# AD8232.net
KiCad netlist of a schematic drawn in Altium Designer
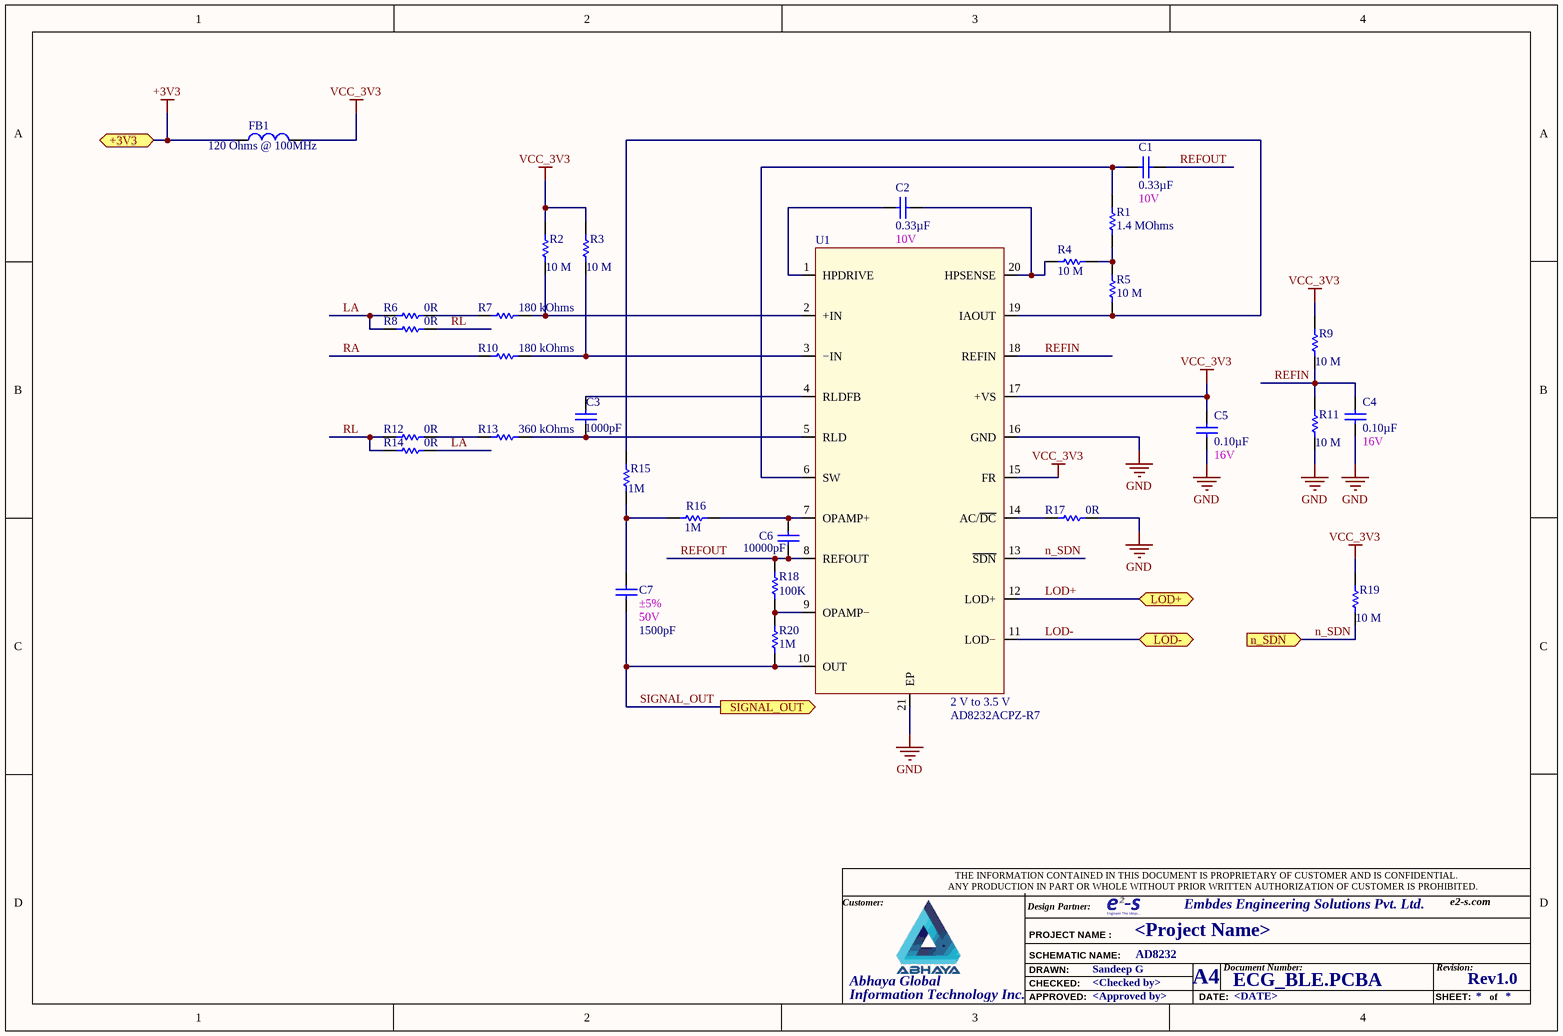
[diagram p0: AD8232.SchDoc]

(export (version "E")
  (design (tool "Eeschema 10.0.6"))
  (components
    (comp (ref "C1")
      (value "0.33µF")
      (footprint "SMDC0402")
      (description "CAP CER 0.33UF 10V X5R 0402")
      (fields
        (field (name "MANUFACTURER") "Samsung Electro-Mechanics")
        (field (name "MANUFACTURER PART NUMBER") "CL05A334KP5NNNC")
        (field (name "1ST AUXILIARY FIELD") "10V")
      )
      (libsource (lib "ECG_BLE") (part "ECA0U33L10V0-SB"))
    )
    (comp (ref "C2")
      (value "0.33µF")
      (footprint "SMDC0402")
      (description "CAP CER 0.33UF 10V X5R 0402")
      (fields
        (field (name "MANUFACTURER") "Samsung Electro-Mechanics")
        (field (name "MANUFACTURER PART NUMBER") "CL05A334KP5NNNC")
        (field (name "1ST AUXILIARY FIELD") "10V")
      )
      (libsource (lib "ECG_BLE") (part "ECA0U33L10V0-SB"))
    )
    (comp (ref "C3")
      (value "1000pF")
      (footprint "SMDC0402")
      (description "CAP CER 1000PF 50V X7R 0402")
      (fields
        (field (name "MANUFACTURER") "KEMET")
        (field (name "MANUFACTURER PART NUMBER") "C0402C102J5RACTU")
      )
      (libsource (lib "ECG_BLE") (part "ECA1N00K50V0-SB"))
    )
    (comp (ref "C4")
      (value "0.10µF")
      (footprint "SMDC0402")
      (description "CAP CER 0.1UF 16V X7R 0402")
      (fields
        (field (name "MANUFACTURER") "Samsung Electro-Mechanics America, Inc.")
        (field (name "MANUFACTURER PART NUMBER") "CL05B104KO5NNNC")
        (field (name "1ST AUXILIARY FIELD") "16V")
      )
      (libsource (lib "Master_ Library") (part "ECA0U10K16V0-1-SB"))
    )
    (comp (ref "C5")
      (value "0.10µF")
      (footprint "SMDC0402")
      (description "CAP CER 0.1UF 16V X7R 0402")
      (fields
        (field (name "MANUFACTURER") "Samsung Electro-Mechanics America, Inc.")
        (field (name "MANUFACTURER PART NUMBER") "CL05B104KO5NNNC")
        (field (name "1ST AUXILIARY FIELD") "16V")
      )
      (libsource (lib "Master_ Library") (part "ECA0U10K16V0-1-SB"))
    )
    (comp (ref "C6")
      (value "10000pF")
      (footprint "SMDCC0402")
      (description "CAP CER 10000PF 50V X7R 0402")
      (fields
        (field (name "MANUFACTURER PART NUMBER") "C0402C103J5RACTU")
        (field (name "MANUFACTURER") "Samsung Electro-Mechanics America, Inc.")
      )
      (libsource (lib "Master_ Library") (part "ECA10N0K50V0-SB"))
    )
    (comp (ref "C7")
      (value "1500pF")
      (footprint "SMDC0402")
      (description "CAP CER 1500PF 50V X7R 0402")
      (fields
        (field (name "MANUFACTURER") "Yageo")
        (field (name "VENDOR PART NUMBER") "311-3763-1-ND")
        (field (name "2ND AUXILIARY FIELD") "±5%")
        (field (name "1ST AUXILIARY FIELD") "50V")
      )
      (libsource (lib "ECG_BLE") (part "ECA1N50K50V0-SB"))
    )
    (comp (ref "FB1")
      (value "120 Ohms @ 100MHz")
      (footprint "Master_Library:SMDL0402")
      (description "FERRITE BEAD 120 OHM 0402 1LN")
      (fields
        (field (name "MANUFACTURER PART NUMBER") "BLM15PX121SN1D")
        (field (name "MANUFACTURER") "Murata Electronics")
      )
      (libsource (lib "ECG_BLE") (part "EMS-BLM15PX121SN1D"))
    )
    (comp (ref "R1")
      (value "1.4 MOhms")
      (footprint "Master_Library:SMDR0402")
      (description "RES 1.4M OHM 1% 1/16W 0402")
      (fields
        (field (name "MANUFACTURER") "Stackpole Electronics Inc")
        (field (name "VENDOR PART NUMBER") "RMCF0402FT1M40CT-ND")
      )
      (libsource (lib "ECG_BLE") (part "ERE1M40G116-SB"))
    )
    (comp (ref "R2")
      (value "10 M")
      (footprint "SMDR0402")
      (description "RES SMD 10M OHM 5% 1/10W 0402")
      (fields
        (field (name "MANUFACTURER PART NUMBER") "ERJ-2GEJ106X")
        (field (name "MANUFACTURER") "Panasonic Electronic Components")
      )
      (libsource (lib "Master_ Library") (part "ERE10M0K110-SB"))
    )
    (comp (ref "R3")
      (value "10 M")
      (footprint "SMDR0402")
      (description "RES SMD 10M OHM 5% 1/10W 0402")
      (fields
        (field (name "MANUFACTURER PART NUMBER") "ERJ-2GEJ106X")
        (field (name "MANUFACTURER") "Panasonic Electronic Components")
      )
      (libsource (lib "Master_ Library") (part "ERE10M0K110-SB"))
    )
    (comp (ref "R4")
      (value "10 M")
      (footprint "SMDR0402")
      (description "RES SMD 10M OHM 5% 1/10W 0402")
      (fields
        (field (name "MANUFACTURER PART NUMBER") "ERJ-2GEJ106X")
        (field (name "MANUFACTURER") "Panasonic Electronic Components")
      )
      (libsource (lib "Master_ Library") (part "ERE10M0K110-SB"))
    )
    (comp (ref "R5")
      (value "10 M")
      (footprint "SMDR0402")
      (description "RES SMD 10M OHM 5% 1/10W 0402")
      (fields
        (field (name "MANUFACTURER PART NUMBER") "ERJ-2GEJ106X")
        (field (name "MANUFACTURER") "Panasonic Electronic Components")
      )
      (libsource (lib "Master_ Library") (part "ERE10M0K110-SB"))
    )
    (comp (ref "R6")
      (value "0R")
      (footprint "Master_Library:SMDR0402")
      (description "RES SMD 0.0OHM JUMPER 1/10W 0402")
      (fields
        (field (name "MANUFACTURER") "Panasonic Electronic Components")
        (field (name "VENDOR PART NUMBER") "P0.0JCT-ND")
      )
      (libsource (lib "Integrated_Master_Library") (part "ERE0R00110-SB"))
    )
    (comp (ref "R7")
      (value "180 kOhms")
      (footprint "Master_Library:SMDR0402")
      (description "RES SMD 180K OHM 1% 1/16W 0402")
      (fields (field (name "MANUFACTURER") "Yageo") (field (name "VENDOR PART NUMBER") "311-180KLRCT-ND"))
      (libsource (lib "ECG_BLE") (part "ERE180KG116-SB"))
    )
    (comp (ref "R8")
      (value "0R")
      (footprint "Master_Library:SMDR0402")
      (description "RES SMD 0.0OHM JUMPER 1/10W 0402")
      (fields
        (field (name "MANUFACTURER") "Panasonic Electronic Components")
        (field (name "VENDOR PART NUMBER") "P0.0JCT-ND")
      )
      (libsource (lib "Integrated_Master_Library") (part "ERE0R00110-SB"))
    )
    (comp (ref "R9")
      (value "10 M")
      (footprint "SMDR0402")
      (description "RES SMD 10M OHM 5% 1/10W 0402")
      (fields
        (field (name "MANUFACTURER PART NUMBER") "ERJ-2GEJ106X")
        (field (name "MANUFACTURER") "Panasonic Electronic Components")
      )
      (libsource (lib "Master_ Library") (part "ERE10M0K110-SB"))
    )
    (comp (ref "R10")
      (value "180 kOhms")
      (footprint "Master_Library:SMDR0402")
      (description "RES SMD 180K OHM 1% 1/16W 0402")
      (fields (field (name "MANUFACTURER") "Yageo") (field (name "VENDOR PART NUMBER") "311-180KLRCT-ND"))
      (libsource (lib "ECG_BLE") (part "ERE180KG116-SB"))
    )
    (comp (ref "R11")
      (value "10 M")
      (footprint "SMDR0402")
      (description "RES SMD 10M OHM 5% 1/10W 0402")
      (fields
        (field (name "MANUFACTURER PART NUMBER") "ERJ-2GEJ106X")
        (field (name "MANUFACTURER") "Panasonic Electronic Components")
      )
      (libsource (lib "Master_ Library") (part "ERE10M0K110-SB"))
    )
    (comp (ref "R12")
      (value "0R")
      (footprint "Master_Library:SMDR0402")
      (description "RES SMD 0.0OHM JUMPER 1/10W 0402")
      (fields
        (field (name "MANUFACTURER") "Panasonic Electronic Components")
        (field (name "VENDOR PART NUMBER") "P0.0JCT-ND")
      )
      (libsource (lib "Integrated_Master_Library") (part "ERE0R00110-SB"))
    )
    (comp (ref "R13")
      (value "360 kOhms")
      (footprint "Master_Library:SMDR0402")
      (description "RES SMD 360K OHM 1% 1/10W 0402")
      (fields
        (field (name "MANUFACTURER") "Panasonic Electronic Components")
        (field (name "VENDOR PART NUMBER") "P360KLCT-ND")
      )
      (libsource (lib "ECG_BLE") (part "ERE360KG110-SB"))
    )
    (comp (ref "R14")
      (value "0R")
      (footprint "Master_Library:SMDR0402")
      (description "RES SMD 0.0OHM JUMPER 1/10W 0402")
      (fields
        (field (name "MANUFACTURER") "Panasonic Electronic Components")
        (field (name "VENDOR PART NUMBER") "P0.0JCT-ND")
      )
      (libsource (lib "Integrated_Master_Library") (part "ERE0R00110-SB"))
    )
    (comp (ref "R15")
      (value "1M")
      (footprint "SMDR0402")
      (description "RES SMD 1M OHM 1% 1/10W 0402")
      (fields
        (field (name "MANUFACTURER PART NUMBER") "ERJ-2RKF1004X")
        (field (name "MANUFACTURER") "Panasonic Electronic Components")
      )
      (libsource (lib "Master_ Library") (part "ERE1M00G110-SB"))
    )
    (comp (ref "R16")
      (value "1M")
      (footprint "SMDR0402")
      (description "RES SMD 1M OHM 1% 1/10W 0402")
      (fields
        (field (name "MANUFACTURER PART NUMBER") "ERJ-2RKF1004X")
        (field (name "MANUFACTURER") "Panasonic Electronic Components")
      )
      (libsource (lib "Master_ Library") (part "ERE1M00G110-SB"))
    )
    (comp (ref "R17")
      (value "0R")
      (footprint "Master_Library:SMDR0402")
      (description "RES SMD 0.0OHM JUMPER 1/10W 0402")
      (fields
        (field (name "MANUFACTURER") "Panasonic Electronic Components")
        (field (name "VENDOR PART NUMBER") "P0.0JCT-ND")
      )
      (libsource (lib "Integrated_Master_Library") (part "ERE0R00110-SB"))
    )
    (comp (ref "R18")
      (value "100K")
      (footprint "SMDRC0402")
      (description "RES SMD 100K OHM 1% 1/10W 0402")
      (fields
        (field (name "MANUFACTURER PART NUMBER") "ERJ-2RKF1003X")
        (field (name "MANUFACTURER") "Panasonic Electronic Components")
      )
      (libsource (lib "Master_ Library") (part "ERE100KG110-SB"))
    )
    (comp (ref "R19")
      (value "10 M")
      (footprint "SMDR0402")
      (description "RES SMD 10M OHM 5% 1/10W 0402")
      (fields
        (field (name "MANUFACTURER PART NUMBER") "ERJ-2GEJ106X")
        (field (name "MANUFACTURER") "Panasonic Electronic Components")
      )
      (libsource (lib "Master_ Library") (part "ERE10M0K110-SB"))
    )
    (comp (ref "R20")
      (value "1M")
      (footprint "SMDR0402")
      (description "RES SMD 1M OHM 1% 1/10W 0402")
      (fields
        (field (name "MANUFACTURER PART NUMBER") "ERJ-2RKF1004X")
        (field (name "MANUFACTURER") "Panasonic Electronic Components")
      )
      (libsource (lib "Master_ Library") (part "ERE1M00G110-SB"))
    )
    (comp (ref "U1")
      (value "AD8232ACPZ-R7")
      (description "Analog Front End - AFE ECG and HRM IC Single Lead")
      (fields
        (field (name "INTERNAL PART NUMBER") "EICADLFCSP-20-****")
        (field (name "MANUFACTURER") "Analog Devices")
        (field (name "1ST AUXILIARY FIELD") "2 V to 3.5 V")
      )
      (libsource (lib "ECG_BLE") (part "EICADLFCSP-20-****"))
    )
  )
  (nets
    (net (code "1") (name "+3V3") (class "Default")
      (node (ref "FB1") (pin "1") (pinfunction "1_1") (pintype "passive"))
    )
    (net (code "2") (name "/LA") (class "Default")
      (node (ref "R14") (pin "2") (pinfunction "2_2") (pintype "passive"))
      (node (ref "R6") (pin "1") (pinfunction "1_1") (pintype "passive"))
      (node (ref "R8") (pin "1") (pinfunction "1_1") (pintype "passive"))
    )
    (net (code "3") (name "/LOD+") (class "Default")
      (node (ref "U1") (pin "12") (pinfunction "LOD+_12") (pintype "passive"))
    )
    (net (code "4") (name "/LOD-") (class "Default")
      (node (ref "U1") (pin "11") (pinfunction "LOD−_11") (pintype "passive"))
    )
    (net (code "5") (name "/RA") (class "Default")
      (node (ref "R10") (pin "1") (pinfunction "1_1") (pintype "passive"))
    )
    (net (code "6") (name "/REFIN") (class "Default")
      (node (ref "C4") (pin "2") (pinfunction "2_2") (pintype "passive"))
      (node (ref "R11") (pin "2") (pinfunction "2_2") (pintype "passive"))
      (node (ref "R9") (pin "1") (pinfunction "1_1") (pintype "passive"))
      (node (ref "U1") (pin "18") (pinfunction "REFIN_18") (pintype "passive"))
    )
    (net (code "7") (name "/REFOUT") (class "Default")
      (node (ref "C1") (pin "2") (pinfunction "2_2") (pintype "passive"))
      (node (ref "C6") (pin "1") (pinfunction "1_1") (pintype "passive"))
      (node (ref "R18") (pin "1") (pinfunction "1_1") (pintype "passive"))
      (node (ref "U1") (pin "8") (pinfunction "REFOUT_8") (pintype "passive"))
    )
    (net (code "8") (name "/RL") (class "Default")
      (node (ref "R12") (pin "1") (pinfunction "1_1") (pintype "passive"))
      (node (ref "R14") (pin "1") (pinfunction "1_1") (pintype "passive"))
      (node (ref "R8") (pin "2") (pinfunction "2_2") (pintype "passive"))
    )
    (net (code "9") (name "/SIGNAL_OUT") (class "Default")
      (node (ref "C7") (pin "1") (pinfunction "1_1") (pintype "passive"))
      (node (ref "R20") (pin "2") (pinfunction "2_2") (pintype "passive"))
      (node (ref "U1") (pin "10") (pinfunction "OUT_10") (pintype "passive"))
    )
    (net (code "10") (name "/n_SDN") (class "Default")
      (node (ref "R19") (pin "1") (pinfunction "1_1") (pintype "passive"))
      (node (ref "U1") (pin "13") (pinfunction "~{SDN}_13") (pintype "passive"))
    )
    (net (code "11") (name "GND") (class "Default")
      (node (ref "C4") (pin "1") (pinfunction "1_1") (pintype "passive"))
      (node (ref "C5") (pin "1") (pinfunction "1_1") (pintype "passive"))
      (node (ref "R11") (pin "1") (pinfunction "1_1") (pintype "passive"))
      (node (ref "R17") (pin "2") (pinfunction "2_2") (pintype "passive"))
      (node (ref "U1") (pin "16") (pinfunction "GND_16") (pintype "passive"))
      (node (ref "U1") (pin "21") (pinfunction "EP_21") (pintype "passive"))
    )
    (net (code "12") (name "Net-(C7-Pad2)") (class "Default")
      (node (ref "C7") (pin "2") (pinfunction "2_2") (pintype "passive"))
      (node (ref "R15") (pin "1") (pinfunction "1_1") (pintype "passive"))
      (node (ref "R16") (pin "2") (pinfunction "2_2") (pintype "passive"))
    )
    (net (code "13") (name "Net-(R1-Pad1)") (class "Default")
      (node (ref "R1") (pin "1") (pinfunction "1_1") (pintype "passive"))
      (node (ref "R4") (pin "1") (pinfunction "1_1") (pintype "passive"))
      (node (ref "R5") (pin "1") (pinfunction "1_1") (pintype "passive"))
    )
    (net (code "14") (name "Net-(R6-Pad2)") (class "Default")
      (node (ref "R6") (pin "2") (pinfunction "2_2") (pintype "passive"))
      (node (ref "R7") (pin "1") (pinfunction "1_1") (pintype "passive"))
    )
    (net (code "15") (name "Net-(R12-Pad2)") (class "Default")
      (node (ref "R12") (pin "2") (pinfunction "2_2") (pintype "passive"))
      (node (ref "R13") (pin "1") (pinfunction "1_1") (pintype "passive"))
    )
    (net (code "16") (name "Net-(U1-+IN)") (class "Default")
      (node (ref "R2") (pin "1") (pinfunction "1_1") (pintype "passive"))
      (node (ref "R7") (pin "2") (pinfunction "2_2") (pintype "passive"))
      (node (ref "U1") (pin "2") (pinfunction "+IN_2") (pintype "passive"))
    )
    (net (code "17") (name "Net-(U1-AC{slash}~{DC})") (class "Default")
      (node (ref "R17") (pin "1") (pinfunction "1_1") (pintype "passive"))
      (node (ref "U1") (pin "14") (pinfunction "AC/~{DC}_14") (pintype "passive"))
    )
    (net (code "18") (name "Net-(U1-HPDRIVE)") (class "Default")
      (node (ref "C2") (pin "1") (pinfunction "1_1") (pintype "passive"))
      (node (ref "U1") (pin "1") (pinfunction "HPDRIVE_1") (pintype "passive"))
    )
    (net (code "19") (name "Net-(U1-HPSENSE)") (class "Default")
      (node (ref "C2") (pin "2") (pinfunction "2_2") (pintype "passive"))
      (node (ref "R4") (pin "2") (pinfunction "2_2") (pintype "passive"))
      (node (ref "U1") (pin "20") (pinfunction "HPSENSE_20") (pintype "passive"))
    )
    (net (code "20") (name "Net-(U1-IAOUT)") (class "Default")
      (node (ref "R15") (pin "2") (pinfunction "2_2") (pintype "passive"))
      (node (ref "R5") (pin "2") (pinfunction "2_2") (pintype "passive"))
      (node (ref "U1") (pin "19") (pinfunction "IAOUT_19") (pintype "passive"))
    )
    (net (code "21") (name "Net-(U1-OPAMP+)") (class "Default")
      (node (ref "C6") (pin "2") (pinfunction "2_2") (pintype "passive"))
      (node (ref "R16") (pin "1") (pinfunction "1_1") (pintype "passive"))
      (node (ref "U1") (pin "7") (pinfunction "OPAMP+_7") (pintype "passive"))
    )
    (net (code "22") (name "Net-(U1-OPAMP−)") (class "Default")
      (node (ref "R18") (pin "2") (pinfunction "2_2") (pintype "passive"))
      (node (ref "R20") (pin "1") (pinfunction "1_1") (pintype "passive"))
      (node (ref "U1") (pin "9") (pinfunction "OPAMP−_9") (pintype "passive"))
    )
    (net (code "23") (name "Net-(U1-RLD)") (class "Default")
      (node (ref "C3") (pin "1") (pinfunction "1_1") (pintype "passive"))
      (node (ref "R13") (pin "2") (pinfunction "2_2") (pintype "passive"))
      (node (ref "U1") (pin "5") (pinfunction "RLD_5") (pintype "passive"))
    )
    (net (code "24") (name "Net-(U1-RLDFB)") (class "Default")
      (node (ref "C3") (pin "2") (pinfunction "2_2") (pintype "passive"))
      (node (ref "U1") (pin "4") (pinfunction "RLDFB_4") (pintype "passive"))
    )
    (net (code "25") (name "Net-(U1-SW)") (class "Default")
      (node (ref "C1") (pin "1") (pinfunction "1_1") (pintype "passive"))
      (node (ref "R1") (pin "2") (pinfunction "2_2") (pintype "passive"))
      (node (ref "U1") (pin "6") (pinfunction "SW_6") (pintype "passive"))
    )
    (net (code "26") (name "Net-(U1-−IN)") (class "Default")
      (node (ref "R10") (pin "2") (pinfunction "2_2") (pintype "passive"))
      (node (ref "R3") (pin "1") (pinfunction "1_1") (pintype "passive"))
      (node (ref "U1") (pin "3") (pinfunction "−IN_3") (pintype "passive"))
    )
    (net (code "27") (name "VCC_3V3") (class "Default")
      (node (ref "C5") (pin "2") (pinfunction "2_2") (pintype "passive"))
      (node (ref "FB1") (pin "2") (pinfunction "2_2") (pintype "passive"))
      (node (ref "R19") (pin "2") (pinfunction "2_2") (pintype "passive"))
      (node (ref "R2") (pin "2") (pinfunction "2_2") (pintype "passive"))
      (node (ref "R3") (pin "2") (pinfunction "2_2") (pintype "passive"))
      (node (ref "R9") (pin "2") (pinfunction "2_2") (pintype "passive"))
      (node (ref "U1") (pin "15") (pinfunction "FR_15") (pintype "passive"))
      (node (ref "U1") (pin "17") (pinfunction "+VS_17") (pintype "passive"))
    )
  )
)
